# Mach_khoa_so_dien_tu_-_Bao.net
KiCad netlist of a schematic drawn in Altium Designer
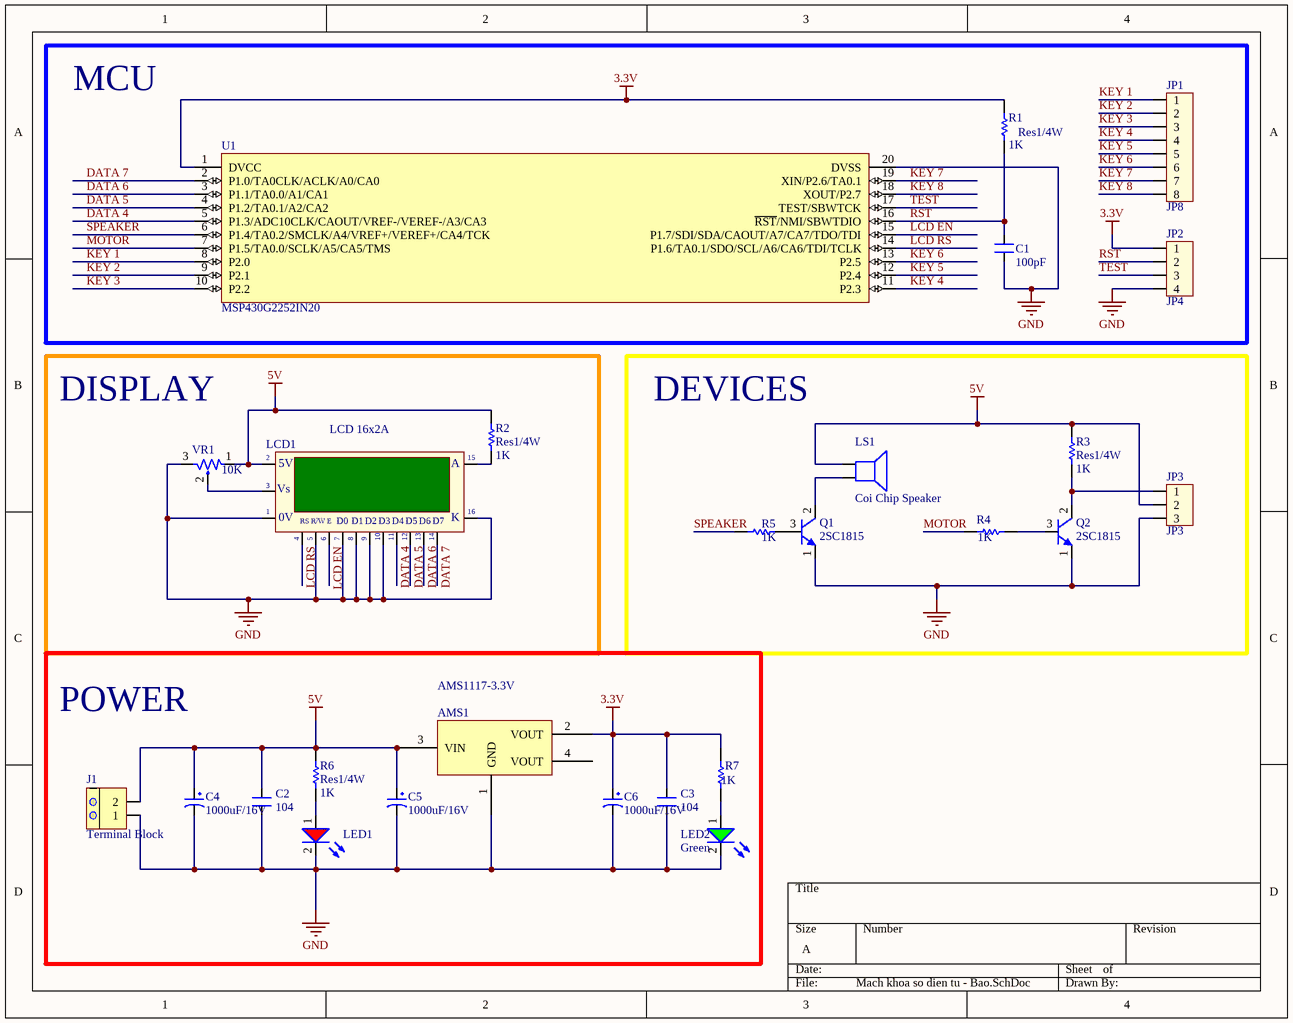
[diagram p0: Mach khoa so dien tu - Bao.SchDoc]

(export (version "E")
  (design (tool "Eeschema 10.0.6"))
  (components
    (comp (ref "AMS1")
      (value "AMS1117-3.3V")
      (footprint "SOT223")
      (description "Dán")
      (libsource (lib "Altium_Lib_by_KhueNguyenCreator") (part "AMS1117 SMD"))
    )
    (comp (ref "C1")
      (value "100pF")
      (footprint "CN1")
      (description "Cap np  1pF - 472pF")
      (libsource (lib "lpson") (part "CN1"))
    )
    (comp (ref "C2")
      (value "104")
      (footprint "CN2")
      (description "Cap np 104 => 105pF")
      (libsource (lib "lpson") (part "CN2"))
    )
    (comp (ref "C3")
      (value "104")
      (footprint "CN2")
      (description "Cap np 104 => 105pF")
      (libsource (lib "lpson") (part "CN2"))
    )
    (comp (ref "C4")
      (value "1000uF/16V")
      (footprint "CP1.5/3.4")
      (description "Cap 1000uF/16V - 220uF/50V")
      (libsource (lib "lpson") (part "CP4"))
    )
    (comp (ref "C5")
      (value "1000uF/16V")
      (footprint "CP1.5/3.4")
      (description "Cap 1000uF/16V - 220uF/50V")
      (libsource (lib "lpson") (part "CP4"))
    )
    (comp (ref "C6")
      (value "1000uF/16V")
      (footprint "CP1.5/3.4")
      (description "Cap 1000uF/16V - 220uF/50V")
      (libsource (lib "lpson") (part "CP4"))
    )
    (comp (ref "J1")
      (value "Terminal Block")
      (footprint "STB02")
      (description "Terminal Block 2 Poles 5.08mm Blue")
      (fields (field (name "Comment") "OSTTC-02-2162"))
      (libsource (lib "lpson") (part "OSTTC-02-2162"))
    )
    (comp (ref "JP1")
      (value "JP8")
      (footprint "CON8")
      (description "Connector 8")
      (libsource (lib "lpson") (part "Con8"))
    )
    (comp (ref "JP2")
      (value "JP4")
      (footprint "CON4")
      (description "Connector 4")
      (libsource (lib "lpson") (part "Con4"))
    )
    (comp (ref "JP3")
      (value "JP3")
      (footprint "CON3")
      (description "Connector 3")
      (libsource (lib "lpson") (part "Con3"))
    )
    (comp (ref "LCD1")
      (value "LCD 16x2A")
      (footprint "LCD16x2")
      (description "LCD dipslay 16 char, 2 line")
      (libsource (lib "lpson") (part "LCD16x2A"))
    )
    (comp (ref "LED1")
      (value "RED LED 5mm")
      (footprint "LED5R")
      (description "LED Red 5mm")
      (fields
        (field (name "MANUFACTURER") "Broadcom Limited")
        (field (name "MANUFACTURER PART NUMBER") "HLMP-3316")
      )
      (libsource (lib "lpson") (part "LED_RED_5MM_1"))
    )
    (comp (ref "LED2")
      (value "Green")
      (footprint "LED5G")
      (description "LED Green 5mm")
      (fields (field (name "Comment") "LED_G_5"))
      (libsource (lib "lpson") (part "LED_GREEN_5MM"))
    )
    (comp (ref "LS1")
      (value "Coi Chip Speaker")
      (footprint "Coi Chip Speacker")
      (description "Còi chip")
      (libsource (lib "Altium_Lib_by_KhueNguyenCreator") (part "Coi Chip Speaker"))
    )
    (comp (ref "Q1")
      (value "2SC1815")
      (footprint "2SC1815")
      (description "Trans NPN 50V 150mA TO-92")
      (libsource (lib "lpson") (part "2SC1815"))
    )
    (comp (ref "Q2")
      (value "2SC1815")
      (footprint "2SC1815")
      (description "Trans NPN 50V 150mA TO-92")
      (libsource (lib "lpson") (part "2SC1815"))
    )
    (comp (ref "R1")
      (value "Res1/4W")
      (footprint "CFR25S")
      (description "Resistor")
      (fields (field (name "ALTIUM_VALUE") "1K") (field (name "PUBLISHER") "Altium Limited"))
      (libsource (lib "lpson") (part "Res1/4W"))
    )
    (comp (ref "R2")
      (value "Res1/4W")
      (footprint "CFR25S")
      (description "Resistor")
      (fields (field (name "ALTIUM_VALUE") "1K") (field (name "PUBLISHER") "Altium Limited"))
      (libsource (lib "lpson") (part "Res1/4W"))
    )
    (comp (ref "R3")
      (value "Res1/4W")
      (footprint "CFR25S")
      (description "Resistor")
      (fields (field (name "ALTIUM_VALUE") "1K") (field (name "PUBLISHER") "Altium Limited"))
      (libsource (lib "lpson") (part "Res1/4W"))
    )
    (comp (ref "R4")
      (value "1K")
      (footprint "CFR25S")
      (description "Resistor")
      (fields (field (name "Comment") "Res1/4W") (field (name "PUBLISHER") "Altium Limited"))
      (libsource (lib "lpson") (part "Res1/4W"))
    )
    (comp (ref "R5")
      (value "1K")
      (footprint "CFR25S")
      (description "Resistor")
      (fields (field (name "Comment") "Res1/4W") (field (name "PUBLISHER") "Altium Limited"))
      (libsource (lib "lpson") (part "Res1/4W"))
    )
    (comp (ref "R6")
      (value "Res1/4W")
      (footprint "CFR25S")
      (description "Resistor")
      (fields (field (name "ALTIUM_VALUE") "1K") (field (name "PUBLISHER") "Altium Limited"))
      (libsource (lib "lpson") (part "Res1/4W"))
    )
    (comp (ref "R7")
      (value "1K")
      (footprint "CFR25S")
      (description "Resistor")
      (fields (field (name "Comment") "Res1/4W") (field (name "PUBLISHER") "Altium Limited"))
      (libsource (lib "lpson") (part "Res1/4W"))
    )
    (comp (ref "U1")
      (value "MSP430G2252IN20")
      (footprint "MSP430G2552")
      (description "MCU 16bit 16KB 1.8-3.6V 16MHz DIP20")
      (libsource (lib "lpson") (part "MSP430G2252IN20"))
    )
    (comp (ref "VR1")
      (value "10K")
      (footprint "VR1")
      (description "Var Resistor")
      (libsource (lib "lpson") (part "VR2"))
    )
  )
  (nets
    (net (code "1") (name "/DATA 4") (class "Default")
      (node (ref "LCD1") (pin "11") (pinfunction "D4_11") (pintype "passive"))
      (node (ref "U1") (pin "5") (pinfunction "P1.3/ADC10CLK/CAOUT/VREF-/VEREF-/A3/CA3_5") (pintype "bidirectional"))
    )
    (net (code "2") (name "/DATA 5") (class "Default")
      (node (ref "LCD1") (pin "12") (pinfunction "D5_12") (pintype "passive"))
      (node (ref "U1") (pin "4") (pinfunction "P1.2/TA0.1/A2/CA2_4") (pintype "bidirectional"))
    )
    (net (code "3") (name "/DATA 6") (class "Default")
      (node (ref "LCD1") (pin "13") (pinfunction "D6_13") (pintype "passive"))
      (node (ref "U1") (pin "3") (pinfunction "P1.1/TA0.0/A1/CA1_3") (pintype "bidirectional"))
    )
    (net (code "4") (name "/DATA 7") (class "Default")
      (node (ref "LCD1") (pin "14") (pinfunction "D7_14") (pintype "passive"))
      (node (ref "U1") (pin "2") (pinfunction "P1.0/TA0CLK/ACLK/A0/CA0_2") (pintype "bidirectional"))
    )
    (net (code "5") (name "/KEY 1") (class "Default")
      (node (ref "JP1") (pin "1") (pinfunction "1_1") (pintype "passive"))
      (node (ref "U1") (pin "8") (pinfunction "P2.0_8") (pintype "bidirectional"))
    )
    (net (code "6") (name "/KEY 2") (class "Default")
      (node (ref "JP1") (pin "2") (pinfunction "2_2") (pintype "passive"))
      (node (ref "U1") (pin "9") (pinfunction "P2.1_9") (pintype "bidirectional"))
    )
    (net (code "7") (name "/KEY 3") (class "Default")
      (node (ref "JP1") (pin "3") (pinfunction "3_3") (pintype "passive"))
      (node (ref "U1") (pin "10") (pinfunction "P2.2_10") (pintype "bidirectional"))
    )
    (net (code "8") (name "/KEY 4") (class "Default")
      (node (ref "JP1") (pin "4") (pinfunction "4_4") (pintype "passive"))
      (node (ref "U1") (pin "11") (pinfunction "P2.3_11") (pintype "bidirectional"))
    )
    (net (code "9") (name "/KEY 5") (class "Default")
      (node (ref "JP1") (pin "5") (pinfunction "5_5") (pintype "passive"))
      (node (ref "U1") (pin "12") (pinfunction "P2.4_12") (pintype "bidirectional"))
    )
    (net (code "10") (name "/KEY 6") (class "Default")
      (node (ref "JP1") (pin "6") (pinfunction "6_6") (pintype "passive"))
      (node (ref "U1") (pin "13") (pinfunction "P2.5_13") (pintype "bidirectional"))
    )
    (net (code "11") (name "/KEY 7") (class "Default")
      (node (ref "JP1") (pin "7") (pinfunction "7_7") (pintype "passive"))
      (node (ref "U1") (pin "19") (pinfunction "XIN/P2.6/TA0.1_19") (pintype "bidirectional"))
    )
    (net (code "12") (name "/KEY 8") (class "Default")
      (node (ref "JP1") (pin "8") (pinfunction "8_8") (pintype "passive"))
      (node (ref "U1") (pin "18") (pinfunction "XOUT/P2.7_18") (pintype "bidirectional"))
    )
    (net (code "13") (name "/LCD EN") (class "Default")
      (node (ref "LCD1") (pin "6") (pinfunction "~{EN}_6") (pintype "passive"))
      (node (ref "U1") (pin "15") (pinfunction "P1.7/SDI/SDA/CAOUT/A7/CA7/TDO/TDI_15") (pintype "bidirectional"))
    )
    (net (code "14") (name "/LCD RS") (class "Default")
      (node (ref "LCD1") (pin "4") (pinfunction "RS_4") (pintype "passive"))
      (node (ref "U1") (pin "14") (pinfunction "P1.6/TA0.1/SDO/SCL/A6/CA6/TDI/TCLK_14") (pintype "bidirectional"))
    )
    (net (code "15") (name "/MOTOR") (class "Default")
      (node (ref "R4") (pin "1") (pinfunction "1_1") (pintype "passive"))
      (node (ref "U1") (pin "7") (pinfunction "P1.5/TA0.0/SCLK/A5/CA5/TMS_7") (pintype "bidirectional"))
    )
    (net (code "16") (name "/RST") (class "Default")
      (node (ref "C1") (pin "1") (pinfunction "1_1") (pintype "passive"))
      (node (ref "JP2") (pin "2") (pinfunction "2_2") (pintype "passive"))
      (node (ref "R1") (pin "1") (pinfunction "1_1") (pintype "passive"))
      (node (ref "U1") (pin "16") (pinfunction "~{RST}/NMI/SBWTDIO_16") (pintype "bidirectional"))
    )
    (net (code "17") (name "/SPEAKER") (class "Default")
      (node (ref "R5") (pin "1") (pinfunction "1_1") (pintype "passive"))
      (node (ref "U1") (pin "6") (pinfunction "P1.4/TA0.2/SMCLK/A4/VREF+/VEREF+/CA4/TCK_6") (pintype "bidirectional"))
    )
    (net (code "18") (name "/TEST") (class "Default")
      (node (ref "JP2") (pin "3") (pinfunction "3_3") (pintype "passive"))
      (node (ref "U1") (pin "17") (pinfunction "TEST/SBWTCK_17") (pintype "bidirectional"))
    )
    (net (code "19") (name "3.3V") (class "Default")
      (node (ref "AMS1") (pin "2") (pinfunction "VOUT_2") (pintype "passive"))
      (node (ref "C3") (pin "2") (pinfunction "2_2") (pintype "passive"))
      (node (ref "C6") (pin "1") (pinfunction "1_1") (pintype "passive"))
      (node (ref "JP2") (pin "1") (pinfunction "1_1") (pintype "passive"))
      (node (ref "R1") (pin "2") (pinfunction "2_2") (pintype "passive"))
      (node (ref "R7") (pin "1") (pinfunction "1_1") (pintype "passive"))
      (node (ref "U1") (pin "1") (pinfunction "DVCC_1") (pintype "power_in"))
    )
    (net (code "20") (name "5V") (class "Default")
      (node (ref "AMS1") (pin "3") (pinfunction "VIN_3") (pintype "passive"))
      (node (ref "C2") (pin "2") (pinfunction "2_2") (pintype "passive"))
      (node (ref "C4") (pin "1") (pinfunction "1_1") (pintype "passive"))
      (node (ref "C5") (pin "1") (pinfunction "1_1") (pintype "passive"))
      (node (ref "J1") (pin "2") (pinfunction "2_2") (pintype "passive"))
      (node (ref "JP3") (pin "2") (pinfunction "2_2") (pintype "passive"))
      (node (ref "LCD1") (pin "2") (pinfunction "VDD_2") (pintype "passive"))
      (node (ref "LS1") (pin "1") (pinfunction "1_1") (pintype "passive"))
      (node (ref "R2") (pin "2") (pinfunction "2_2") (pintype "passive"))
      (node (ref "R3") (pin "1") (pinfunction "1_1") (pintype "passive"))
      (node (ref "R6") (pin "1") (pinfunction "1_1") (pintype "passive"))
      (node (ref "VR1") (pin "1") (pinfunction "1_1") (pintype "passive"))
    )
    (net (code "21") (name "GND") (class "Default")
      (node (ref "AMS1") (pin "1") (pinfunction "GND_1") (pintype "passive"))
      (node (ref "C1") (pin "2") (pinfunction "2_2") (pintype "passive"))
      (node (ref "C2") (pin "1") (pinfunction "1_1") (pintype "passive"))
      (node (ref "C3") (pin "1") (pinfunction "1_1") (pintype "passive"))
      (node (ref "C4") (pin "2") (pinfunction "2_2") (pintype "passive"))
      (node (ref "C5") (pin "2") (pinfunction "2_2") (pintype "passive"))
      (node (ref "C6") (pin "2") (pinfunction "2_2") (pintype "passive"))
      (node (ref "J1") (pin "1") (pinfunction "1_1") (pintype "passive"))
      (node (ref "JP2") (pin "4") (pinfunction "4_4") (pintype "passive"))
      (node (ref "JP3") (pin "3") (pinfunction "3_3") (pintype "passive"))
      (node (ref "LCD1") (pin "1") (pinfunction "GND_1") (pintype "passive"))
      (node (ref "LCD1") (pin "10") (pinfunction "D3_10") (pintype "passive"))
      (node (ref "LCD1") (pin "16") (pinfunction "K_16") (pintype "passive"))
      (node (ref "LCD1") (pin "5") (pinfunction "R/~{W}_5") (pintype "passive"))
      (node (ref "LCD1") (pin "7") (pinfunction "D0_7") (pintype "passive"))
      (node (ref "LCD1") (pin "8") (pinfunction "D1_8") (pintype "passive"))
      (node (ref "LCD1") (pin "9") (pinfunction "D2_9") (pintype "passive"))
      (node (ref "LED1") (pin "2") (pinfunction "K_2") (pintype "passive"))
      (node (ref "LED2") (pin "2") (pinfunction "K_2") (pintype "passive"))
      (node (ref "Q1") (pin "1") (pinfunction "E_1") (pintype "passive"))
      (node (ref "Q2") (pin "1") (pinfunction "E_1") (pintype "passive"))
      (node (ref "U1") (pin "20") (pinfunction "DVSS_20") (pintype "power_in"))
      (node (ref "VR1") (pin "3") (pinfunction "3_3") (pintype "passive"))
    )
    (net (code "22") (name "Net-(LCD1-A)") (class "Default")
      (node (ref "LCD1") (pin "15") (pinfunction "A_15") (pintype "passive"))
      (node (ref "R2") (pin "1") (pinfunction "1_1") (pintype "passive"))
    )
    (net (code "23") (name "Net-(LCD1-VEE)") (class "Default")
      (node (ref "LCD1") (pin "3") (pinfunction "VEE_3") (pintype "passive"))
      (node (ref "VR1") (pin "2") (pinfunction "2_2") (pintype "passive"))
    )
    (net (code "24") (name "Net-(LED1-A)") (class "Default")
      (node (ref "LED1") (pin "1") (pinfunction "A_1") (pintype "passive"))
      (node (ref "R6") (pin "2") (pinfunction "2_2") (pintype "passive"))
    )
    (net (code "25") (name "Net-(LED2-A)") (class "Default")
      (node (ref "LED2") (pin "1") (pinfunction "A_1") (pintype "passive"))
      (node (ref "R7") (pin "2") (pinfunction "2_2") (pintype "passive"))
    )
    (net (code "26") (name "Net-(Q1-B)") (class "Default")
      (node (ref "Q1") (pin "3") (pinfunction "B_3") (pintype "passive"))
      (node (ref "R5") (pin "2") (pinfunction "2_2") (pintype "passive"))
    )
    (net (code "27") (name "Net-(Q1-C)") (class "Default")
      (node (ref "LS1") (pin "2") (pinfunction "2_2") (pintype "passive"))
      (node (ref "Q1") (pin "2") (pinfunction "C_2") (pintype "passive"))
    )
    (net (code "28") (name "Net-(Q2-B)") (class "Default")
      (node (ref "Q2") (pin "3") (pinfunction "B_3") (pintype "passive"))
      (node (ref "R4") (pin "2") (pinfunction "2_2") (pintype "passive"))
    )
    (net (code "29") (name "Net-(Q2-C)") (class "Default")
      (node (ref "JP3") (pin "1") (pinfunction "1_1") (pintype "passive"))
      (node (ref "Q2") (pin "2") (pinfunction "C_2") (pintype "passive"))
      (node (ref "R3") (pin "2") (pinfunction "2_2") (pintype "passive"))
    )
    (net (code "30") (name "unconnected-(AMS1-VOUT-Pad4)") (class "Default")
      (node (ref "AMS1") (pin "4") (pinfunction "VOUT_4") (pintype "passive"))
    )
  )
)
